# motordriver_output_board_01.net
KiCad netlist of a schematic drawn in EAGLE
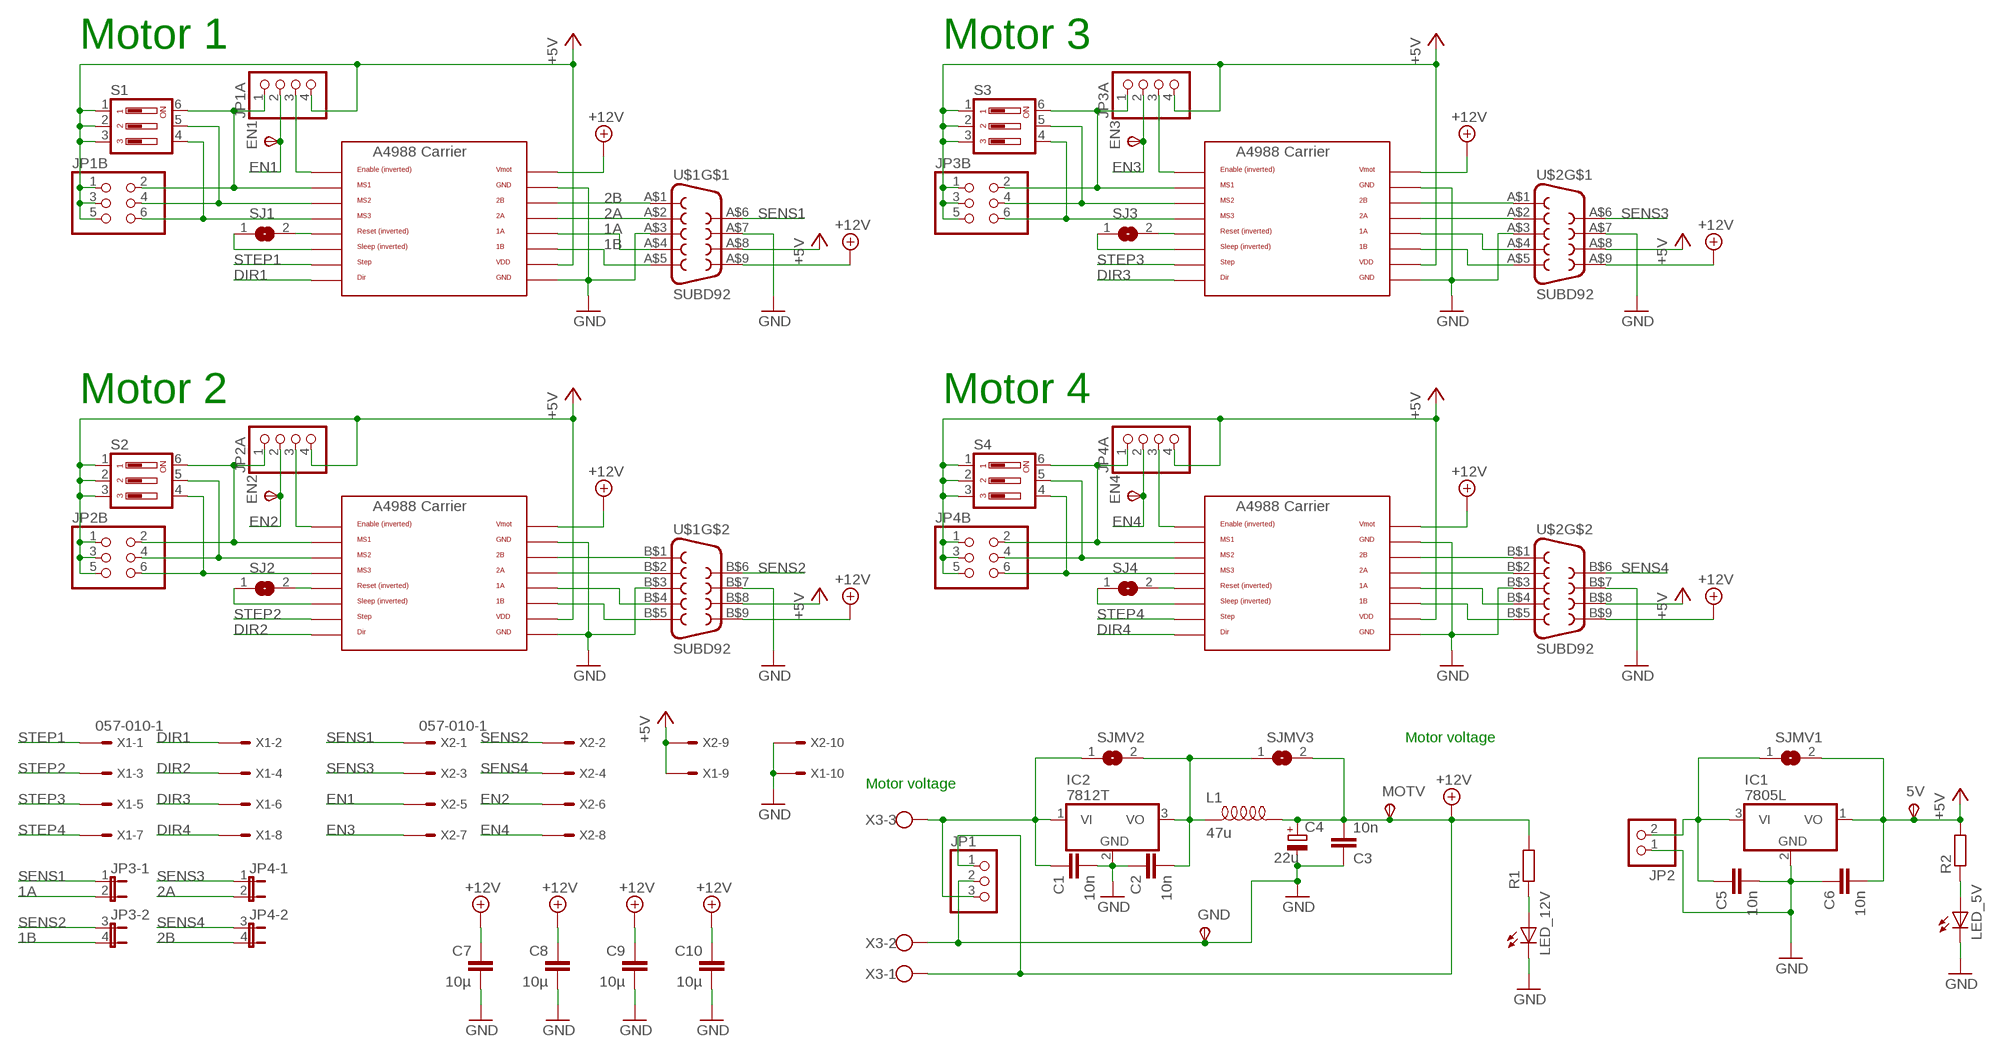
[diagram p0: schematic, sheet 1]

(export (version "E")
  (design (tool "Eeschema 10.0.6"))
  (components
    (comp (ref "5V")
      (value "TPSPAD1-13")
      (footprint "eagle-import:P1-13")
      (libsource (lib "eagle-import") (part "TPSPAD1-13"))
    )
    (comp (ref "C1")
      (value "10n")
      (footprint "eagle-import:C0805")
      (libsource (lib "eagle-import") (part "C-EUC0805"))
    )
    (comp (ref "C2")
      (value "10n")
      (footprint "eagle-import:C0805")
      (libsource (lib "eagle-import") (part "C-EUC0805"))
    )
    (comp (ref "C3")
      (value "10n")
      (footprint "eagle-import:C0805")
      (libsource (lib "eagle-import") (part "C-EUC0805"))
    )
    (comp (ref "C4")
      (value "22u")
      (footprint "eagle-import:153CLV-0605")
      (libsource (lib "eagle-import") (part "CPOL-EU153CLV-0605"))
    )
    (comp (ref "C5")
      (value "10n")
      (footprint "eagle-import:C0805")
      (libsource (lib "eagle-import") (part "C-EUC0805"))
    )
    (comp (ref "C6")
      (value "10n")
      (footprint "eagle-import:C0805")
      (libsource (lib "eagle-import") (part "C-EUC0805"))
    )
    (comp (ref "C7")
      (value "10µ")
      (footprint "eagle-import:C0805")
      (libsource (lib "eagle-import") (part "C-EUC0805"))
    )
    (comp (ref "C8")
      (value "10µ")
      (footprint "eagle-import:C0805")
      (libsource (lib "eagle-import") (part "C-EUC0805"))
    )
    (comp (ref "C9")
      (value "10µ")
      (footprint "eagle-import:C0805")
      (libsource (lib "eagle-import") (part "C-EUC0805"))
    )
    (comp (ref "C10")
      (value "10µ")
      (footprint "eagle-import:C0805")
      (libsource (lib "eagle-import") (part "C-EUC0805"))
    )
    (comp (ref "EN1")
      (value "TPSPAD1-13")
      (footprint "eagle-import:P1-13")
      (libsource (lib "eagle-import") (part "TPSPAD1-13"))
    )
    (comp (ref "EN2")
      (value "TPSPAD1-13")
      (footprint "eagle-import:P1-13")
      (libsource (lib "eagle-import") (part "TPSPAD1-13"))
    )
    (comp (ref "EN3")
      (value "TPSPAD1-13")
      (footprint "eagle-import:P1-13")
      (libsource (lib "eagle-import") (part "TPSPAD1-13"))
    )
    (comp (ref "EN4")
      (value "TPSPAD1-13")
      (footprint "eagle-import:P1-13")
      (libsource (lib "eagle-import") (part "TPSPAD1-13"))
    )
    (comp (ref "GND")
      (value "TPSPAD1-13")
      (footprint "eagle-import:P1-13")
      (libsource (lib "eagle-import") (part "TPSPAD1-13"))
    )
    (comp (ref "IC1")
      (value "7805L")
      (footprint "eagle-import:TO92")
      (libsource (lib "eagle-import") (part "78L05"))
    )
    (comp (ref "IC2")
      (value "7812T")
      (footprint "eagle-import:TO220H")
      (libsource (lib "eagle-import") (part "78T12"))
    )
    (comp (ref "JP1")
      (value "PINHD-1X3")
      (footprint "eagle-import:1X03")
      (libsource (lib "eagle-import") (part "PINHD-1X3"))
    )
    (comp (ref "JP1A")
      (value "PINHD-1X4")
      (footprint "eagle-import:1X04")
      (libsource (lib "eagle-import") (part "PINHD-1X4"))
    )
    (comp (ref "JP1B")
      (value "PINHD-2X3")
      (footprint "eagle-import:2X03")
      (libsource (lib "eagle-import") (part "PINHD-2X3"))
    )
    (comp (ref "JP2")
      (value "PINHD-1X2")
      (footprint "eagle-import:1X02")
      (libsource (lib "eagle-import") (part "PINHD-1X2"))
    )
    (comp (ref "JP2A")
      (value "PINHD-1X4")
      (footprint "eagle-import:1X04")
      (libsource (lib "eagle-import") (part "PINHD-1X4"))
    )
    (comp (ref "JP2B")
      (value "PINHD-2X3")
      (footprint "eagle-import:2X03")
      (libsource (lib "eagle-import") (part "PINHD-2X3"))
    )
    (comp (ref "JP3")
      (value "JP2QE")
      (footprint "eagle-import:JP2Q")
      (libsource (lib "eagle-import") (part "JP2QE"))
    )
    (comp (ref "JP3A")
      (value "PINHD-1X4")
      (footprint "eagle-import:1X04")
      (libsource (lib "eagle-import") (part "PINHD-1X4"))
    )
    (comp (ref "JP3B")
      (value "PINHD-2X3")
      (footprint "eagle-import:2X03")
      (libsource (lib "eagle-import") (part "PINHD-2X3"))
    )
    (comp (ref "JP4")
      (value "JP2QE")
      (footprint "eagle-import:JP2Q")
      (libsource (lib "eagle-import") (part "JP2QE"))
    )
    (comp (ref "JP4A")
      (value "PINHD-1X4")
      (footprint "eagle-import:1X04")
      (libsource (lib "eagle-import") (part "PINHD-1X4"))
    )
    (comp (ref "JP4B")
      (value "PINHD-2X3")
      (footprint "eagle-import:2X03")
      (libsource (lib "eagle-import") (part "PINHD-2X3"))
    )
    (comp (ref "L1")
      (value "47u")
      (footprint "eagle-import:D10F")
      (libsource (lib "eagle-import") (part "A814AY-220M"))
    )
    (comp (ref "LED_5V")
      (value "LEDCHIP-LED0805")
      (footprint "eagle-import:CHIP-LED0805")
      (libsource (lib "eagle-import") (part "LEDCHIP-LED0805"))
    )
    (comp (ref "LED_12V")
      (value "LEDCHIP-LED0805")
      (footprint "eagle-import:CHIP-LED0805")
      (libsource (lib "eagle-import") (part "LEDCHIP-LED0805"))
    )
    (comp (ref "MOTDRV1")
      (value "A4988BREAKOUT")
      (footprint "eagle-import:A4988BREAKOUT")
      (libsource (lib "eagle-import") (part "A4988BREAKOUT"))
    )
    (comp (ref "MOTDRV2")
      (value "A4988BREAKOUT")
      (footprint "eagle-import:A4988BREAKOUT")
      (libsource (lib "eagle-import") (part "A4988BREAKOUT"))
    )
    (comp (ref "MOTDRV3")
      (value "A4988BREAKOUT")
      (footprint "eagle-import:A4988BREAKOUT")
      (libsource (lib "eagle-import") (part "A4988BREAKOUT"))
    )
    (comp (ref "MOTDRV4")
      (value "A4988BREAKOUT")
      (footprint "eagle-import:A4988BREAKOUT")
      (libsource (lib "eagle-import") (part "A4988BREAKOUT"))
    )
    (comp (ref "MOTV")
      (value "TPSPAD1-13")
      (footprint "eagle-import:P1-13")
      (libsource (lib "eagle-import") (part "TPSPAD1-13"))
    )
    (comp (ref "R1")
      (value "R-EU_M0805")
      (footprint "eagle-import:M0805")
      (libsource (lib "eagle-import") (part "R-EU_M0805"))
    )
    (comp (ref "R2")
      (value "R-EU_M0805")
      (footprint "eagle-import:M0805")
      (libsource (lib "eagle-import") (part "R-EU_M0805"))
    )
    (comp (ref "S1")
      (value "DIP03YL")
      (footprint "eagle-import:DIP03YL")
      (libsource (lib "eagle-import") (part "DIP03YL"))
    )
    (comp (ref "S2")
      (value "DIP03YL")
      (footprint "eagle-import:DIP03YL")
      (libsource (lib "eagle-import") (part "DIP03YL"))
    )
    (comp (ref "S3")
      (value "DIP03YL")
      (footprint "eagle-import:DIP03YL")
      (libsource (lib "eagle-import") (part "DIP03YL"))
    )
    (comp (ref "S4")
      (value "DIP03YL")
      (footprint "eagle-import:DIP03YL")
      (libsource (lib "eagle-import") (part "DIP03YL"))
    )
    (comp (ref "SJ1") (value "SJ") (footprint "eagle-import:SJ") (libsource (lib "eagle-import") (part "SJ")))
    (comp (ref "SJ2") (value "SJ") (footprint "eagle-import:SJ") (libsource (lib "eagle-import") (part "SJ")))
    (comp (ref "SJ3") (value "SJ") (footprint "eagle-import:SJ") (libsource (lib "eagle-import") (part "SJ")))
    (comp (ref "SJ4") (value "SJ") (footprint "eagle-import:SJ") (libsource (lib "eagle-import") (part "SJ")))
    (comp (ref "SJMV1")
      (value "SJW")
      (footprint "eagle-import:SJW")
      (libsource (lib "eagle-import") (part "SJW"))
    )
    (comp (ref "SJMV2")
      (value "SJW")
      (footprint "eagle-import:SJW")
      (libsource (lib "eagle-import") (part "SJW"))
    )
    (comp (ref "SJMV3")
      (value "SJW")
      (footprint "eagle-import:SJW")
      (libsource (lib "eagle-import") (part "SJW"))
    )
    (comp (ref "U$1")
      (value "SUBD92")
      (footprint "eagle-import:SUBD9-2")
      (libsource (lib "eagle-import") (part "SUBD92"))
    )
    (comp (ref "U$2")
      (value "SUBD92")
      (footprint "eagle-import:SUBD9-2")
      (libsource (lib "eagle-import") (part "SUBD92"))
    )
    (comp (ref "X1")
      (value "057-010-1")
      (footprint "eagle-import:057-010-1")
      (libsource (lib "eagle-import") (part "057-010-1"))
    )
    (comp (ref "X2")
      (value "057-010-1")
      (footprint "eagle-import:057-010-1")
      (libsource (lib "eagle-import") (part "057-010-1"))
    )
    (comp (ref "X3")
      (value "W237-103")
      (footprint "eagle-import:W237-103")
      (fields (field (name "MPN") "237-103"))
      (libsource (lib "eagle-import") (part "W237-103"))
    )
  )
  (nets
    (net (code "1") (name "+5V") (class "Default")
      (node (ref "5V") (pin "TP") (pinfunction "PP_TP") (pintype "input"))
      (node (ref "C6") (pin "2") (pinfunction "2_2") (pintype "passive"))
      (node (ref "IC1") (pin "1") (pinfunction "VO_1") (pintype "passive"))
      (node (ref "JP1A") (pin "4") (pinfunction "4_4") (pintype "passive"))
      (node (ref "JP1B") (pin "1") (pinfunction "1_1") (pintype "passive"))
      (node (ref "JP1B") (pin "3") (pinfunction "3_3") (pintype "passive"))
      (node (ref "JP1B") (pin "5") (pinfunction "5_5") (pintype "passive"))
      (node (ref "JP2A") (pin "4") (pinfunction "4_4") (pintype "passive"))
      (node (ref "JP2B") (pin "1") (pinfunction "1_1") (pintype "passive"))
      (node (ref "JP2B") (pin "3") (pinfunction "3_3") (pintype "passive"))
      (node (ref "JP2B") (pin "5") (pinfunction "5_5") (pintype "passive"))
      (node (ref "JP3A") (pin "4") (pinfunction "4_4") (pintype "passive"))
      (node (ref "JP3B") (pin "1") (pinfunction "1_1") (pintype "passive"))
      (node (ref "JP3B") (pin "3") (pinfunction "3_3") (pintype "passive"))
      (node (ref "JP3B") (pin "5") (pinfunction "5_5") (pintype "passive"))
      (node (ref "JP4A") (pin "4") (pinfunction "4_4") (pintype "passive"))
      (node (ref "JP4B") (pin "1") (pinfunction "1_1") (pintype "passive"))
      (node (ref "JP4B") (pin "3") (pinfunction "3_3") (pintype "passive"))
      (node (ref "JP4B") (pin "5") (pinfunction "5_5") (pintype "passive"))
      (node (ref "MOTDRV1") (pin "VDD") (pinfunction "VDD_VDD") (pintype "power_in"))
      (node (ref "MOTDRV2") (pin "VDD") (pinfunction "VDD_VDD") (pintype "power_in"))
      (node (ref "MOTDRV3") (pin "VDD") (pinfunction "VDD_VDD") (pintype "power_in"))
      (node (ref "MOTDRV4") (pin "VDD") (pinfunction "VDD_VDD") (pintype "power_in"))
      (node (ref "R2") (pin "2") (pinfunction "2_2") (pintype "passive"))
      (node (ref "S1") (pin "1") (pinfunction "1_1") (pintype "passive"))
      (node (ref "S1") (pin "2") (pinfunction "2_2") (pintype "passive"))
      (node (ref "S1") (pin "3") (pinfunction "3_3") (pintype "passive"))
      (node (ref "S2") (pin "1") (pinfunction "1_1") (pintype "passive"))
      (node (ref "S2") (pin "2") (pinfunction "2_2") (pintype "passive"))
      (node (ref "S2") (pin "3") (pinfunction "3_3") (pintype "passive"))
      (node (ref "S3") (pin "1") (pinfunction "1_1") (pintype "passive"))
      (node (ref "S3") (pin "2") (pinfunction "2_2") (pintype "passive"))
      (node (ref "S3") (pin "3") (pinfunction "3_3") (pintype "passive"))
      (node (ref "S4") (pin "1") (pinfunction "1_1") (pintype "passive"))
      (node (ref "S4") (pin "2") (pinfunction "2_2") (pintype "passive"))
      (node (ref "S4") (pin "3") (pinfunction "3_3") (pintype "passive"))
      (node (ref "SJMV1") (pin "2") (pinfunction "2_2") (pintype "passive"))
      (node (ref "U$1") (pin "A$8") (pinfunction "8_A$8") (pintype "passive"))
      (node (ref "U$1") (pin "B$8") (pinfunction "8_B$8") (pintype "passive"))
      (node (ref "U$2") (pin "A$8") (pinfunction "8_A$8") (pintype "passive"))
      (node (ref "U$2") (pin "B$8") (pinfunction "8_B$8") (pintype "passive"))
      (node (ref "X1") (pin "9") (pinfunction "S_9") (pintype "passive"))
      (node (ref "X2") (pin "9") (pinfunction "S_9") (pintype "passive"))
    )
    (net (code "2") (name "+12V") (class "Default")
      (node (ref "C10") (pin "1") (pinfunction "1_1") (pintype "passive"))
      (node (ref "C3") (pin "2") (pinfunction "2_2") (pintype "passive"))
      (node (ref "C4") (pin "+") (pinfunction "+_+") (pintype "passive"))
      (node (ref "C7") (pin "1") (pinfunction "1_1") (pintype "passive"))
      (node (ref "C8") (pin "1") (pinfunction "1_1") (pintype "passive"))
      (node (ref "C9") (pin "1") (pinfunction "1_1") (pintype "passive"))
      (node (ref "JP1") (pin "1") (pinfunction "1_1") (pintype "passive"))
      (node (ref "L1") (pin "2") (pinfunction "2_2") (pintype "passive"))
      (node (ref "MOTDRV1") (pin "VMOT") (pinfunction "VMOT_VMOT") (pintype "power_in"))
      (node (ref "MOTDRV2") (pin "VMOT") (pinfunction "VMOT_VMOT") (pintype "power_in"))
      (node (ref "MOTDRV3") (pin "VMOT") (pinfunction "VMOT_VMOT") (pintype "power_in"))
      (node (ref "MOTDRV4") (pin "VMOT") (pinfunction "VMOT_VMOT") (pintype "power_in"))
      (node (ref "MOTV") (pin "TP") (pinfunction "PP_TP") (pintype "input"))
      (node (ref "R1") (pin "2") (pinfunction "2_2") (pintype "passive"))
      (node (ref "SJMV3") (pin "2") (pinfunction "2_2") (pintype "passive"))
      (node (ref "U$1") (pin "A$9") (pinfunction "9_A$9") (pintype "passive"))
      (node (ref "U$1") (pin "B$9") (pinfunction "9_B$9") (pintype "passive"))
      (node (ref "U$2") (pin "A$9") (pinfunction "9_A$9") (pintype "passive"))
      (node (ref "U$2") (pin "B$9") (pinfunction "9_B$9") (pintype "passive"))
      (node (ref "X3") (pin "1") (pinfunction "KL_1") (pintype "passive"))
    )
    (net (code "3") (name "/1A") (class "Default")
      (node (ref "JP3") (pin "2") (pinfunction "2_2") (pintype "passive"))
      (node (ref "MOTDRV1") (pin "1A") (pinfunction "1A_1A") (pintype "output"))
      (node (ref "U$1") (pin "A$4") (pinfunction "4_A$4") (pintype "passive"))
    )
    (net (code "4") (name "/1B") (class "Default")
      (node (ref "JP3") (pin "4") (pinfunction "2_4") (pintype "passive"))
      (node (ref "MOTDRV1") (pin "1B") (pinfunction "1B_1B") (pintype "output"))
      (node (ref "U$1") (pin "A$5") (pinfunction "5_A$5") (pintype "passive"))
    )
    (net (code "5") (name "/2A") (class "Default")
      (node (ref "JP4") (pin "2") (pinfunction "2_2") (pintype "passive"))
      (node (ref "MOTDRV1") (pin "2A") (pinfunction "2A_2A") (pintype "output"))
      (node (ref "U$1") (pin "A$2") (pinfunction "2_A$2") (pintype "passive"))
    )
    (net (code "6") (name "/2B") (class "Default")
      (node (ref "JP4") (pin "4") (pinfunction "2_4") (pintype "passive"))
      (node (ref "MOTDRV1") (pin "2B") (pinfunction "2B_2B") (pintype "output"))
      (node (ref "U$1") (pin "A$1") (pinfunction "1_A$1") (pintype "passive"))
    )
    (net (code "7") (name "/DIR1") (class "Default")
      (node (ref "MOTDRV1") (pin "DIR") (pinfunction "DIR_DIR") (pintype "input"))
      (node (ref "X1") (pin "2") (pinfunction "S_2") (pintype "passive"))
    )
    (net (code "8") (name "/DIR2") (class "Default")
      (node (ref "MOTDRV2") (pin "DIR") (pinfunction "DIR_DIR") (pintype "input"))
      (node (ref "X1") (pin "4") (pinfunction "S_4") (pintype "passive"))
    )
    (net (code "9") (name "/DIR3") (class "Default")
      (node (ref "MOTDRV3") (pin "DIR") (pinfunction "DIR_DIR") (pintype "input"))
      (node (ref "X1") (pin "6") (pinfunction "S_6") (pintype "passive"))
    )
    (net (code "10") (name "/DIR4") (class "Default")
      (node (ref "MOTDRV4") (pin "DIR") (pinfunction "DIR_DIR") (pintype "input"))
      (node (ref "X1") (pin "8") (pinfunction "S_8") (pintype "passive"))
    )
    (net (code "11") (name "/EN1") (class "Default")
      (node (ref "EN1") (pin "TP") (pinfunction "PP_TP") (pintype "input"))
      (node (ref "JP1A") (pin "2") (pinfunction "2_2") (pintype "passive"))
      (node (ref "X2") (pin "5") (pinfunction "S_5") (pintype "passive"))
    )
    (net (code "12") (name "/EN2") (class "Default")
      (node (ref "EN2") (pin "TP") (pinfunction "PP_TP") (pintype "input"))
      (node (ref "JP2A") (pin "2") (pinfunction "2_2") (pintype "passive"))
      (node (ref "X2") (pin "6") (pinfunction "S_6") (pintype "passive"))
    )
    (net (code "13") (name "/EN3") (class "Default")
      (node (ref "EN3") (pin "TP") (pinfunction "PP_TP") (pintype "input"))
      (node (ref "JP3A") (pin "2") (pinfunction "2_2") (pintype "passive"))
      (node (ref "X2") (pin "7") (pinfunction "S_7") (pintype "passive"))
    )
    (net (code "14") (name "/EN4") (class "Default")
      (node (ref "EN4") (pin "TP") (pinfunction "PP_TP") (pintype "input"))
      (node (ref "JP4A") (pin "2") (pinfunction "2_2") (pintype "passive"))
      (node (ref "X2") (pin "8") (pinfunction "S_8") (pintype "passive"))
    )
    (net (code "15") (name "/SENS1") (class "Default")
      (node (ref "JP3") (pin "1") (pinfunction "1_1") (pintype "passive"))
      (node (ref "U$1") (pin "A$6") (pinfunction "6_A$6") (pintype "passive"))
      (node (ref "X2") (pin "1") (pinfunction "S_1") (pintype "passive"))
    )
    (net (code "16") (name "/SENS2") (class "Default")
      (node (ref "JP3") (pin "3") (pinfunction "1_3") (pintype "passive"))
      (node (ref "U$1") (pin "B$6") (pinfunction "6_B$6") (pintype "passive"))
      (node (ref "X2") (pin "2") (pinfunction "S_2") (pintype "passive"))
    )
    (net (code "17") (name "/SENS3") (class "Default")
      (node (ref "JP4") (pin "1") (pinfunction "1_1") (pintype "passive"))
      (node (ref "U$2") (pin "A$6") (pinfunction "6_A$6") (pintype "passive"))
      (node (ref "X2") (pin "3") (pinfunction "S_3") (pintype "passive"))
    )
    (net (code "18") (name "/SENS4") (class "Default")
      (node (ref "JP4") (pin "3") (pinfunction "1_3") (pintype "passive"))
      (node (ref "U$2") (pin "B$6") (pinfunction "6_B$6") (pintype "passive"))
      (node (ref "X2") (pin "4") (pinfunction "S_4") (pintype "passive"))
    )
    (net (code "19") (name "/STEP1") (class "Default")
      (node (ref "MOTDRV1") (pin "STEP") (pinfunction "STEP_STEP") (pintype "input"))
      (node (ref "X1") (pin "1") (pinfunction "S_1") (pintype "passive"))
    )
    (net (code "20") (name "/STEP2") (class "Default")
      (node (ref "MOTDRV2") (pin "STEP") (pinfunction "STEP_STEP") (pintype "input"))
      (node (ref "X1") (pin "3") (pinfunction "S_3") (pintype "passive"))
    )
    (net (code "21") (name "/STEP3") (class "Default")
      (node (ref "MOTDRV3") (pin "STEP") (pinfunction "STEP_STEP") (pintype "input"))
      (node (ref "X1") (pin "5") (pinfunction "S_5") (pintype "passive"))
    )
    (net (code "22") (name "/STEP4") (class "Default")
      (node (ref "MOTDRV4") (pin "STEP") (pinfunction "STEP_STEP") (pintype "input"))
      (node (ref "X1") (pin "7") (pinfunction "S_7") (pintype "passive"))
    )
    (net (code "23") (name "GND") (class "Default")
      (node (ref "C1") (pin "2") (pinfunction "2_2") (pintype "passive"))
      (node (ref "C10") (pin "2") (pinfunction "2_2") (pintype "passive"))
      (node (ref "C2") (pin "1") (pinfunction "1_1") (pintype "passive"))
      (node (ref "C3") (pin "1") (pinfunction "1_1") (pintype "passive"))
      (node (ref "C4") (pin "-") (pinfunction "-_-") (pintype "passive"))
      (node (ref "C5") (pin "2") (pinfunction "2_2") (pintype "passive"))
      (node (ref "C6") (pin "1") (pinfunction "1_1") (pintype "passive"))
      (node (ref "C7") (pin "2") (pinfunction "2_2") (pintype "passive"))
      (node (ref "C8") (pin "2") (pinfunction "2_2") (pintype "passive"))
      (node (ref "C9") (pin "2") (pinfunction "2_2") (pintype "passive"))
      (node (ref "GND") (pin "TP") (pinfunction "PP_TP") (pintype "input"))
      (node (ref "IC1") (pin "2") (pinfunction "GND_2") (pintype "passive"))
      (node (ref "IC2") (pin "2") (pinfunction "GND_2") (pintype "passive"))
      (node (ref "JP1") (pin "2") (pinfunction "2_2") (pintype "passive"))
      (node (ref "JP2") (pin "1") (pinfunction "1_1") (pintype "passive"))
      (node (ref "LED_12V") (pin "C") (pinfunction "C_C") (pintype "passive"))
      (node (ref "LED_5V") (pin "C") (pinfunction "C_C") (pintype "passive"))
      (node (ref "MOTDRV1") (pin "GND") (pinfunction "GND_GND") (pintype "power_in"))
      (node (ref "MOTDRV1") (pin "GND@0") (pinfunction "GND_GND@0") (pintype "power_in"))
      (node (ref "MOTDRV2") (pin "GND") (pinfunction "GND_GND") (pintype "power_in"))
      (node (ref "MOTDRV2") (pin "GND@0") (pinfunction "GND_GND@0") (pintype "power_in"))
      (node (ref "MOTDRV3") (pin "GND") (pinfunction "GND_GND") (pintype "power_in"))
      (node (ref "MOTDRV3") (pin "GND@0") (pinfunction "GND_GND@0") (pintype "power_in"))
      (node (ref "MOTDRV4") (pin "GND") (pinfunction "GND_GND") (pintype "power_in"))
      (node (ref "MOTDRV4") (pin "GND@0") (pinfunction "GND_GND@0") (pintype "power_in"))
      (node (ref "U$1") (pin "A$3") (pinfunction "3_A$3") (pintype "passive"))
      (node (ref "U$1") (pin "A$7") (pinfunction "7_A$7") (pintype "passive"))
      (node (ref "U$1") (pin "B$3") (pinfunction "3_B$3") (pintype "passive"))
      (node (ref "U$1") (pin "B$7") (pinfunction "7_B$7") (pintype "passive"))
      (node (ref "U$2") (pin "A$3") (pinfunction "3_A$3") (pintype "passive"))
      (node (ref "U$2") (pin "A$7") (pinfunction "7_A$7") (pintype "passive"))
      (node (ref "U$2") (pin "B$3") (pinfunction "3_B$3") (pintype "passive"))
      (node (ref "U$2") (pin "B$7") (pinfunction "7_B$7") (pintype "passive"))
      (node (ref "X1") (pin "10") (pinfunction "S_10") (pintype "passive"))
      (node (ref "X2") (pin "10") (pinfunction "S_10") (pintype "passive"))
      (node (ref "X3") (pin "2") (pinfunction "KL_2") (pintype "passive"))
    )
    (net (code "24") (name "Net-(IC1-VI)") (class "Default")
      (node (ref "C5") (pin "1") (pinfunction "1_1") (pintype "passive"))
      (node (ref "IC1") (pin "3") (pinfunction "VI_3") (pintype "input"))
      (node (ref "JP2") (pin "2") (pinfunction "2_2") (pintype "passive"))
      (node (ref "SJMV1") (pin "1") (pinfunction "1_1") (pintype "passive"))
    )
    (net (code "25") (name "Net-(IC2-VI)") (class "Default")
      (node (ref "C1") (pin "1") (pinfunction "1_1") (pintype "passive"))
      (node (ref "IC2") (pin "1") (pinfunction "VI_1") (pintype "input"))
      (node (ref "JP1") (pin "3") (pinfunction "3_3") (pintype "passive"))
      (node (ref "SJMV2") (pin "1") (pinfunction "1_1") (pintype "passive"))
      (node (ref "X3") (pin "3") (pinfunction "KL_3") (pintype "passive"))
    )
    (net (code "26") (name "Net-(IC2-VO)") (class "Default")
      (node (ref "C2") (pin "2") (pinfunction "2_2") (pintype "passive"))
      (node (ref "IC2") (pin "3") (pinfunction "VO_3") (pintype "passive"))
      (node (ref "L1") (pin "1") (pinfunction "1_1") (pintype "passive"))
      (node (ref "SJMV2") (pin "2") (pinfunction "2_2") (pintype "passive"))
      (node (ref "SJMV3") (pin "1") (pinfunction "1_1") (pintype "passive"))
    )
    (net (code "27") (name "Net-(JP1A-Pad1)") (class "Default")
      (node (ref "JP1A") (pin "1") (pinfunction "1_1") (pintype "passive"))
      (node (ref "JP1B") (pin "2") (pinfunction "2_2") (pintype "passive"))
      (node (ref "MOTDRV1") (pin "MS1") (pinfunction "MS1_MS1") (pintype "input"))
      (node (ref "S1") (pin "6") (pinfunction "6_6") (pintype "passive"))
    )
    (net (code "28") (name "Net-(JP1A-Pad3)") (class "Default")
      (node (ref "JP1A") (pin "3") (pinfunction "3_3") (pintype "passive"))
      (node (ref "MOTDRV1") (pin "EN") (pinfunction "EN_EN") (pintype "input"))
    )
    (net (code "29") (name "Net-(JP1B-Pad4)") (class "Default")
      (node (ref "JP1B") (pin "4") (pinfunction "4_4") (pintype "passive"))
      (node (ref "MOTDRV1") (pin "MS2") (pinfunction "MS2_MS2") (pintype "input"))
      (node (ref "S1") (pin "5") (pinfunction "5_5") (pintype "passive"))
    )
    (net (code "30") (name "Net-(JP1B-Pad6)") (class "Default")
      (node (ref "JP1B") (pin "6") (pinfunction "6_6") (pintype "passive"))
      (node (ref "MOTDRV1") (pin "MS3") (pinfunction "MS3_MS3") (pintype "input"))
      (node (ref "S1") (pin "4") (pinfunction "4_4") (pintype "passive"))
    )
    (net (code "31") (name "Net-(JP2A-Pad1)") (class "Default")
      (node (ref "JP2A") (pin "1") (pinfunction "1_1") (pintype "passive"))
      (node (ref "JP2B") (pin "2") (pinfunction "2_2") (pintype "passive"))
      (node (ref "MOTDRV2") (pin "MS1") (pinfunction "MS1_MS1") (pintype "input"))
      (node (ref "S2") (pin "6") (pinfunction "6_6") (pintype "passive"))
    )
    (net (code "32") (name "Net-(JP2A-Pad3)") (class "Default")
      (node (ref "JP2A") (pin "3") (pinfunction "3_3") (pintype "passive"))
      (node (ref "MOTDRV2") (pin "EN") (pinfunction "EN_EN") (pintype "input"))
    )
    (net (code "33") (name "Net-(JP2B-Pad4)") (class "Default")
      (node (ref "JP2B") (pin "4") (pinfunction "4_4") (pintype "passive"))
      (node (ref "MOTDRV2") (pin "MS2") (pinfunction "MS2_MS2") (pintype "input"))
      (node (ref "S2") (pin "5") (pinfunction "5_5") (pintype "passive"))
    )
    (net (code "34") (name "Net-(JP2B-Pad6)") (class "Default")
      (node (ref "JP2B") (pin "6") (pinfunction "6_6") (pintype "passive"))
      (node (ref "MOTDRV2") (pin "MS3") (pinfunction "MS3_MS3") (pintype "input"))
      (node (ref "S2") (pin "4") (pinfunction "4_4") (pintype "passive"))
    )
    (net (code "35") (name "Net-(JP3A-Pad1)") (class "Default")
      (node (ref "JP3A") (pin "1") (pinfunction "1_1") (pintype "passive"))
      (node (ref "JP3B") (pin "2") (pinfunction "2_2") (pintype "passive"))
      (node (ref "MOTDRV3") (pin "MS1") (pinfunction "MS1_MS1") (pintype "input"))
      (node (ref "S3") (pin "6") (pinfunction "6_6") (pintype "passive"))
    )
    (net (code "36") (name "Net-(JP3A-Pad3)") (class "Default")
      (node (ref "JP3A") (pin "3") (pinfunction "3_3") (pintype "passive"))
      (node (ref "MOTDRV3") (pin "EN") (pinfunction "EN_EN") (pintype "input"))
    )
    (net (code "37") (name "Net-(JP3B-Pad4)") (class "Default")
      (node (ref "JP3B") (pin "4") (pinfunction "4_4") (pintype "passive"))
      (node (ref "MOTDRV3") (pin "MS2") (pinfunction "MS2_MS2") (pintype "input"))
      (node (ref "S3") (pin "5") (pinfunction "5_5") (pintype "passive"))
    )
    (net (code "38") (name "Net-(JP3B-Pad6)") (class "Default")
      (node (ref "JP3B") (pin "6") (pinfunction "6_6") (pintype "passive"))
      (node (ref "MOTDRV3") (pin "MS3") (pinfunction "MS3_MS3") (pintype "input"))
      (node (ref "S3") (pin "4") (pinfunction "4_4") (pintype "passive"))
    )
    (net (code "39") (name "Net-(JP4A-Pad1)") (class "Default")
      (node (ref "JP4A") (pin "1") (pinfunction "1_1") (pintype "passive"))
      (node (ref "JP4B") (pin "2") (pinfunction "2_2") (pintype "passive"))
      (node (ref "MOTDRV4") (pin "MS1") (pinfunction "MS1_MS1") (pintype "input"))
      (node (ref "S4") (pin "6") (pinfunction "6_6") (pintype "passive"))
    )
    (net (code "40") (name "Net-(JP4A-Pad3)") (class "Default")
      (node (ref "JP4A") (pin "3") (pinfunction "3_3") (pintype "passive"))
      (node (ref "MOTDRV4") (pin "EN") (pinfunction "EN_EN") (pintype "input"))
    )
    (net (code "41") (name "Net-(JP4B-Pad4)") (class "Default")
      (node (ref "JP4B") (pin "4") (pinfunction "4_4") (pintype "passive"))
      (node (ref "MOTDRV4") (pin "MS2") (pinfunction "MS2_MS2") (pintype "input"))
      (node (ref "S4") (pin "5") (pinfunction "5_5") (pintype "passive"))
    )
    (net (code "42") (name "Net-(JP4B-Pad6)") (class "Default")
      (node (ref "JP4B") (pin "6") (pinfunction "6_6") (pintype "passive"))
      (node (ref "MOTDRV4") (pin "MS3") (pinfunction "MS3_MS3") (pintype "input"))
      (node (ref "S4") (pin "4") (pinfunction "4_4") (pintype "passive"))
    )
    (net (code "43") (name "Net-(LED_5V-PadA)") (class "Default")
      (node (ref "LED_5V") (pin "A") (pinfunction "A_A") (pintype "passive"))
      (node (ref "R2") (pin "1") (pinfunction "1_1") (pintype "passive"))
    )
    (net (code "44") (name "Net-(LED_12V-PadA)") (class "Default")
      (node (ref "LED_12V") (pin "A") (pinfunction "A_A") (pintype "passive"))
      (node (ref "R1") (pin "1") (pinfunction "1_1") (pintype "passive"))
    )
    (net (code "45") (name "Net-(MOTDRV1-PadRST)") (class "Default")
      (node (ref "MOTDRV1") (pin "RST") (pinfunction "RST_RST") (pintype "input"))
      (node (ref "SJ1") (pin "2") (pinfunction "2_2") (pintype "passive"))
    )
    (net (code "46") (name "Net-(MOTDRV1-SLEEP)") (class "Default")
      (node (ref "MOTDRV1") (pin "SLP") (pinfunction "SLEEP_SLP") (pintype "input"))
      (node (ref "SJ1") (pin "1") (pinfunction "1_1") (pintype "passive"))
    )
    (net (code "47") (name "Net-(MOTDRV2-PadRST)") (class "Default")
      (node (ref "MOTDRV2") (pin "RST") (pinfunction "RST_RST") (pintype "input"))
      (node (ref "SJ2") (pin "2") (pinfunction "2_2") (pintype "passive"))
    )
    (net (code "48") (name "Net-(MOTDRV2-SLEEP)") (class "Default")
      (node (ref "MOTDRV2") (pin "SLP") (pinfunction "SLEEP_SLP") (pintype "input"))
      (node (ref "SJ2") (pin "1") (pinfunction "1_1") (pintype "passive"))
    )
    (net (code "49") (name "Net-(MOTDRV3-PadRST)") (class "Default")
      (node (ref "MOTDRV3") (pin "RST") (pinfunction "RST_RST") (pintype "input"))
      (node (ref "SJ3") (pin "2") (pinfunction "2_2") (pintype "passive"))
    )
    (net (code "50") (name "Net-(MOTDRV3-SLEEP)") (class "Default")
      (node (ref "MOTDRV3") (pin "SLP") (pinfunction "SLEEP_SLP") (pintype "input"))
      (node (ref "SJ3") (pin "1") (pinfunction "1_1") (pintype "passive"))
    )
    (net (code "51") (name "Net-(MOTDRV4-PadRST)") (class "Default")
      (node (ref "MOTDRV4") (pin "RST") (pinfunction "RST_RST") (pintype "input"))
      (node (ref "SJ4") (pin "2") (pinfunction "2_2") (pintype "passive"))
    )
    (net (code "52") (name "Net-(MOTDRV4-SLEEP)") (class "Default")
      (node (ref "MOTDRV4") (pin "SLP") (pinfunction "SLEEP_SLP") (pintype "input"))
      (node (ref "SJ4") (pin "1") (pinfunction "1_1") (pintype "passive"))
    )
    (net (code "53") (name "Net-(U$1B-1)") (class "Default")
      (node (ref "MOTDRV2") (pin "2B") (pinfunction "2B_2B") (pintype "output"))
      (node (ref "U$1") (pin "B$1") (pinfunction "1_B$1") (pintype "passive"))
    )
    (net (code "54") (name "Net-(U$1B-2)") (class "Default")
      (node (ref "MOTDRV2") (pin "2A") (pinfunction "2A_2A") (pintype "output"))
      (node (ref "U$1") (pin "B$2") (pinfunction "2_B$2") (pintype "passive"))
    )
    (net (code "55") (name "Net-(U$1B-4)") (class "Default")
      (node (ref "MOTDRV2") (pin "1A") (pinfunction "1A_1A") (pintype "output"))
      (node (ref "U$1") (pin "B$4") (pinfunction "4_B$4") (pintype "passive"))
    )
    (net (code "56") (name "Net-(U$1B-5)") (class "Default")
      (node (ref "MOTDRV2") (pin "1B") (pinfunction "1B_1B") (pintype "output"))
      (node (ref "U$1") (pin "B$5") (pinfunction "5_B$5") (pintype "passive"))
    )
    (net (code "57") (name "Net-(U$2A-1)") (class "Default")
      (node (ref "MOTDRV3") (pin "2B") (pinfunction "2B_2B") (pintype "output"))
      (node (ref "U$2") (pin "A$1") (pinfunction "1_A$1") (pintype "passive"))
    )
    (net (code "58") (name "Net-(U$2A-2)") (class "Default")
      (node (ref "MOTDRV3") (pin "2A") (pinfunction "2A_2A") (pintype "output"))
      (node (ref "U$2") (pin "A$2") (pinfunction "2_A$2") (pintype "passive"))
    )
    (net (code "59") (name "Net-(U$2A-4)") (class "Default")
      (node (ref "MOTDRV3") (pin "1A") (pinfunction "1A_1A") (pintype "output"))
      (node (ref "U$2") (pin "A$4") (pinfunction "4_A$4") (pintype "passive"))
    )
    (net (code "60") (name "Net-(U$2A-5)") (class "Default")
      (node (ref "MOTDRV3") (pin "1B") (pinfunction "1B_1B") (pintype "output"))
      (node (ref "U$2") (pin "A$5") (pinfunction "5_A$5") (pintype "passive"))
    )
    (net (code "61") (name "Net-(U$2B-1)") (class "Default")
      (node (ref "MOTDRV4") (pin "2B") (pinfunction "2B_2B") (pintype "output"))
      (node (ref "U$2") (pin "B$1") (pinfunction "1_B$1") (pintype "passive"))
    )
    (net (code "62") (name "Net-(U$2B-2)") (class "Default")
      (node (ref "MOTDRV4") (pin "2A") (pinfunction "2A_2A") (pintype "output"))
      (node (ref "U$2") (pin "B$2") (pinfunction "2_B$2") (pintype "passive"))
    )
    (net (code "63") (name "Net-(U$2B-4)") (class "Default")
      (node (ref "MOTDRV4") (pin "1A") (pinfunction "1A_1A") (pintype "output"))
      (node (ref "U$2") (pin "B$4") (pinfunction "4_B$4") (pintype "passive"))
    )
    (net (code "64") (name "Net-(U$2B-5)") (class "Default")
      (node (ref "MOTDRV4") (pin "1B") (pinfunction "1B_1B") (pintype "output"))
      (node (ref "U$2") (pin "B$5") (pinfunction "5_B$5") (pintype "passive"))
    )
  )
)
